# USB-UART-Converter.net
KiCad netlist of a schematic drawn in Altium Designer
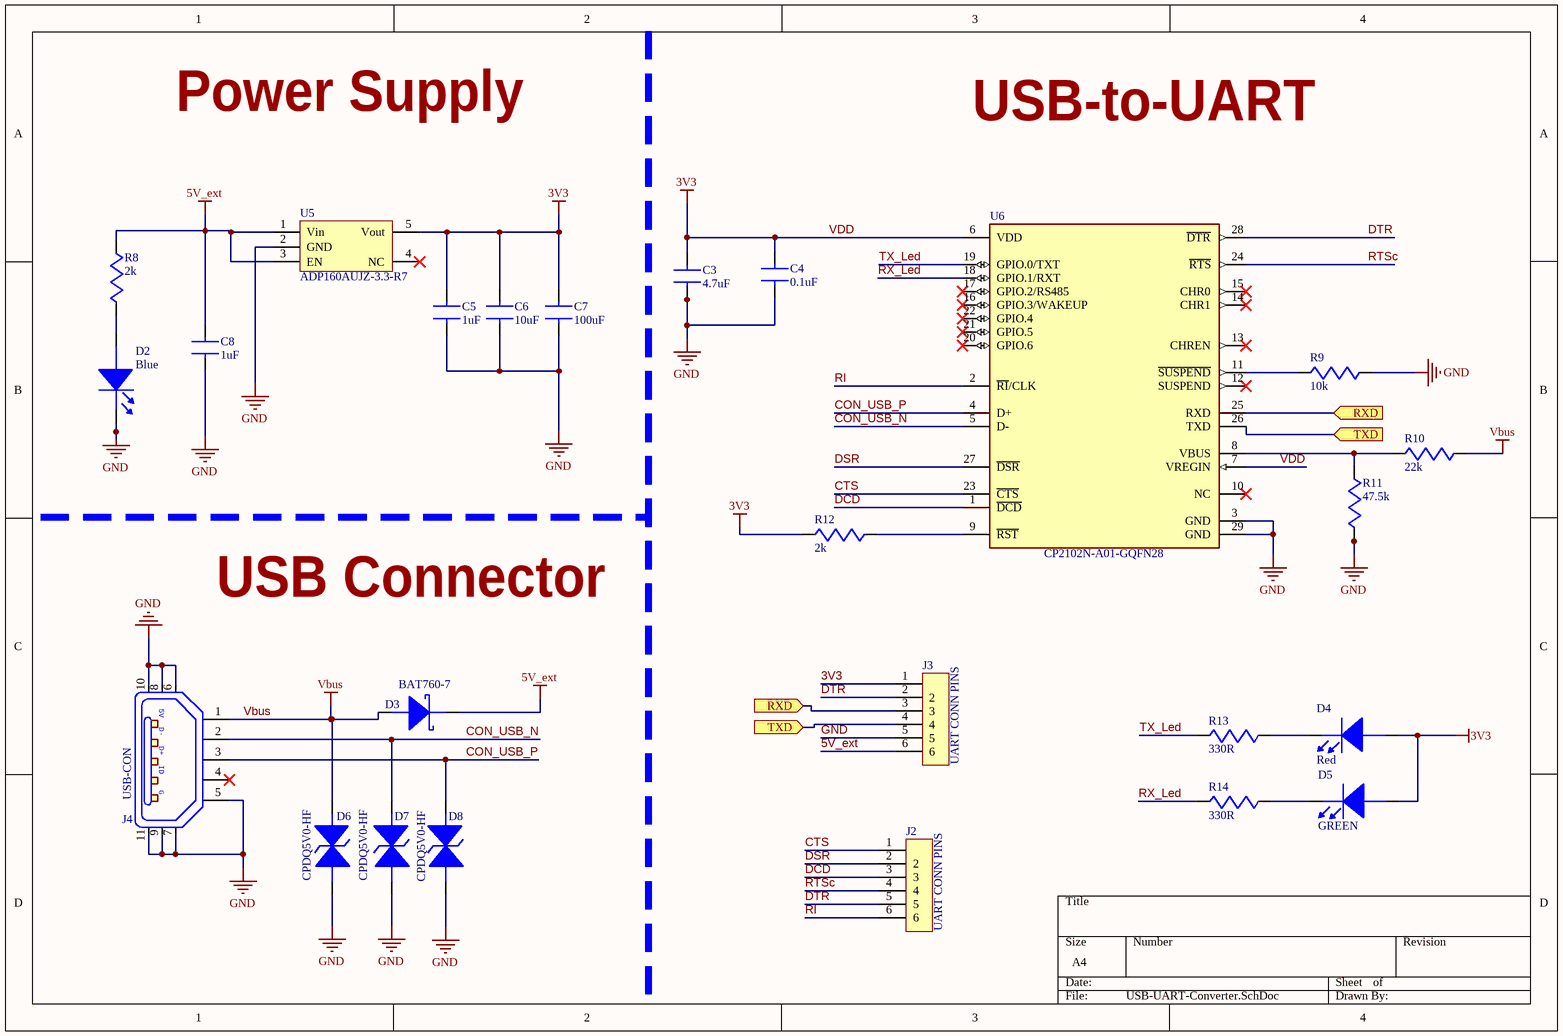
[diagram p0: USB-UART-Converter.SchDoc]

(export (version "E")
  (design (tool "Eeschema 10.0.6"))
  (components
    (comp (ref "C3")
      (value "4.7uF")
      (footprint "C0603")
      (fields
        (field (name "MANUFACTURER") "KEMET")
        (field (name "MANUFACTURER PART NUMBER") "C0603C475K9PACTU")
        (field (name "TOLERANCE") "10%")
      )
      (libsource (lib "Iot_board_schlib") (part "C0603C475K9PACTU"))
    )
    (comp (ref "C4")
      (value "0.1uF")
      (footprint "C0603")
      (fields
        (field (name "MANUFACTURER") "KEMET")
        (field (name "MANUFACTURER PART NUMBER") "C0603C104K5RACTU")
        (field (name "TOLERANCE") "10%")
      )
      (libsource (lib "Iot_board_schlib") (part "C0603C104K5RACTU"))
    )
    (comp (ref "C5")
      (value "1uF")
      (footprint "C0603")
      (description "Cap Ceramic 1uF 10V X5R 10% SMD 0603 85°C Paper T/R")
      (fields
        (field (name "MANUFACTURER") "KEMET")
        (field (name "MANUFACTURER PART NUMBER") "C0603C105K8PACTU")
      )
      (libsource (lib "Iot_board_schlib") (part "C0603C105K8PACTU"))
    )
    (comp (ref "C6")
      (value "10uF")
      (footprint "C0603")
      (description "KEMET - C0603C106M9PACTU - CAP, MLCC, X5R, 10UF, 6.3V, 0603")
      (fields
        (field (name "MANUFACTURER") "KEMET")
        (field (name "MANUFACTURER PART NUMBER") "C0603C106M9PACTU")
      )
      (libsource (lib "Iot_board_schlib") (part "C0603C106M9PACTU"))
    )
    (comp (ref "C7")
      (value "100uF")
      (footprint "C1206")
      (description "KEMET - C1206C107M9PACTU - CAP, 100µF, 6.3V, 20%, X5R, 1206")
      (fields
        (field (name "MANUFACTURER") "KEMET")
        (field (name "MANUFACTURER PART NUMBER") "C1206C107M9PACTU")
      )
      (libsource (lib "Iot_board_schlib") (part "C1206C107M9PACTU"))
    )
    (comp (ref "C8")
      (value "1uF")
      (footprint "C0603")
      (description "Cap Ceramic 1uF 10V X5R 10% SMD 0603 85°C Paper T/R")
      (fields
        (field (name "MANUFACTURER") "KEMET")
        (field (name "MANUFACTURER PART NUMBER") "C0603C105K8PACTU")
      )
      (libsource (lib "Iot_board_schlib") (part "C0603C105K8PACTU"))
    )
    (comp (ref "D2")
      (value "Blue")
      (footprint "LED_0603")
      (description "LED BLUE CLEAR 0603 SMD")
      (fields
        (field (name "MANUFACTURER") "Vishay Lite-On")
        (field (name "MANUFACTURER PART NUMBER") "LTST-C191TBKT")
      )
      (libsource (lib "Iot_board_schlib") (part "LTST-C191TBKT"))
    )
    (comp (ref "D3")
      (value "BAT760-7")
      (footprint "SOD323")
      (description "DIODE SCHOTTKY 30V 1A SOD323")
      (fields (field (name "MANUFACTURER") "Diodes"))
      (libsource (lib "usb_uart_Schlib") (part "BAT760-7"))
    )
    (comp (ref "D4")
      (value "Red")
      (footprint "LED_0603")
      (description "AVAGO TECHNOLOGIES - HSMS-C190 - LED, RED, 10MCD, 626NM")
      (fields
        (field (name "MANUFACTURER") "Broadcom Avago")
        (field (name "MANUFACTURER PART NUMBER") "HSMS-C190")
      )
      (libsource (lib "Iot_board_schlib") (part "HSMS-C190"))
    )
    (comp (ref "D5")
      (value "GREEN")
      (footprint "LED_0603")
      (description "LED Uni-Color Green 572nm 2-Pin Chip 0603(1608Metric) T/R")
      (fields
        (field (name "MANUFACTURER") "Osram Opto")
        (field (name "MANUFACTURER PART NUMBER") "LGL29K-G2J1-24-Z")
      )
      (libsource (lib "usb_uart_Schlib") (part "LGL29K-G2J1-24-Z"))
    )
    (comp (ref "D6")
      (value "CPDQ5V0-HF")
      (footprint "SOD-923F")
      (description "TVS DIODE 5V 18.6V 0402/SOD923F")
      (fields (field (name "MANUFACTURER") "Comchip"))
      (libsource (lib "usb_uart_Schlib") (part "CPDQ5V0-HF"))
    )
    (comp (ref "D7")
      (value "CPDQ5V0-HF")
      (footprint "SOD-923F")
      (description "TVS DIODE 5V 18.6V 0402/SOD923F")
      (fields (field (name "MANUFACTURER") "Comchip"))
      (libsource (lib "usb_uart_Schlib") (part "CPDQ5V0-HF"))
    )
    (comp (ref "D8")
      (value "CPDQ5V0-HF")
      (footprint "SOD-923F")
      (description "TVS DIODE 5V 18.6V 0402/SOD923F")
      (fields (field (name "MANUFACTURER") "Comchip"))
      (libsource (lib "usb_uart_Schlib") (part "CPDQ5V0-HF"))
    )
    (comp (ref "J2")
      (value "UART CONN PINS")
      (footprint "HDR_FEMALE_1x6_2.54mm")
      (fields
        (field (name "MANUFACTURER") "Amphenol FCI")
        (field (name "MANUFACTURER PART NUMBER") "66951-010LF")
      )
      (libsource (lib "usb_uart_Schlib") (part "UART CONN PINS"))
    )
    (comp (ref "J3")
      (value "UART CONN PINS")
      (footprint "HDR_FEMALE_1x6_2.54mm")
      (fields
        (field (name "MANUFACTURER") "Amphenol FCI")
        (field (name "MANUFACTURER PART NUMBER") "66951-010LF")
      )
      (libsource (lib "usb_uart_Schlib") (part "UART CONN PINS"))
    )
    (comp (ref "J4")
      (value "USB-CON")
      (footprint "10118193")
      (description "CONN USB MICRO B RECPT SMT R/A")
      (fields
        (field (name "MANUFACTURER") "Amphenol FCI")
        (field (name "MANUFACTURER PART NUMBER") "10118193-0001LF")
      )
      (libsource (lib "usb_uart_Schlib") (part "10118193-0001LF"))
    )
    (comp (ref "R8")
      (value "2k")
      (footprint "R0603")
      (description "D11/CRCW0603 100 2K 1% ET1 e3")
      (fields
        (field (name "MANUFACTURER") "Vishay")
        (field (name "MANUFACTURER PART NUMBER") "CRCW06032K00FKEA")
      )
      (libsource (lib "Iot_board_schlib") (part "CRCW06032K00FKEA"))
    )
    (comp (ref "R9")
      (value "10k")
      (footprint "R0603")
      (fields
        (field (name "MANUFACTURER") "Vishay")
        (field (name "MANUFACTURER PART NUMBER") "CRCW060310K0FKEA")
        (field (name "TOLERANCE") "1%")
      )
      (libsource (lib "Iot_board_schlib") (part "CRCW060310K0FKEA"))
    )
    (comp (ref "R10")
      (value "22k")
      (footprint "R0603")
      (fields
        (field (name "MANUFACTURER") "Vishay")
        (field (name "MANUFACTURER PART NUMBER") "CRCW060322K0FKEA")
        (field (name "TOLERANCE") "1%")
      )
      (libsource (lib "Iot_board_schlib") (part "CRCW060322K0FKEA"))
    )
    (comp (ref "R11")
      (value "47.5k")
      (footprint "R0603")
      (description "Resistor;  Thick Film;  47.5 Kilohms;  0.1 W;  1%;  SMT;  0603;  TCR 37 ppm/DegC")
      (fields
        (field (name "MANUFACTURER") "Vishay")
        (field (name "MANUFACTURER PART NUMBER") "CRCW060347K5FKEA")
      )
      (libsource (lib "Iot_board_schlib") (part "CRCW060347K5FKEA"))
    )
    (comp (ref "R12")
      (value "2k")
      (footprint "R0603")
      (description "D11/CRCW0603 100 2K 1% ET1 e3")
      (fields
        (field (name "MANUFACTURER") "Vishay")
        (field (name "MANUFACTURER PART NUMBER") "CRCW06032K00FKEA")
      )
      (libsource (lib "Iot_board_schlib") (part "CRCW06032K00FKEA"))
    )
    (comp (ref "R13")
      (value "330R")
      (footprint "R0603")
      (description "Res Thick Film 0603 330K Ohm 1% 1/10W 100ppm/C Molded SMD Paper T/R")
      (fields
        (field (name "MANUFACTURER") "Vishay")
        (field (name "MANUFACTURER PART NUMBER") "CRCW0603330KFKEA")
      )
      (libsource (lib "Iot_board_schlib") (part "CRCW0603330KFKEA"))
    )
    (comp (ref "R14")
      (value "330R")
      (footprint "R0603")
      (description "Res Thick Film 0603 330K Ohm 1% 1/10W 100ppm/C Molded SMD Paper T/R")
      (fields
        (field (name "MANUFACTURER") "Vishay")
        (field (name "MANUFACTURER PART NUMBER") "CRCW0603330KFKEA")
      )
      (libsource (lib "Iot_board_schlib") (part "CRCW0603330KFKEA"))
    )
    (comp (ref "U5")
      (value "ADP160AUJZ-3.3-R7")
      (footprint "SOT95")
      (fields (field (name "MANUFACTURER") "Analog Devices"))
      (libsource (lib "Iot_board_schlib") (part "ADP160AUJZ-3.3-R7"))
    )
    (comp (ref "U6")
      (value "CP2102N-A01-GQFN28")
      (footprint "FP-CP2102N-A01-GQFN28-IPC_A")
      (description "IC BRIDGE USB TO UART 28QFN")
      (fields (field (name "MANUFACTURER") "Silicon Labs"))
      (libsource (lib "usb_uart_Schlib") (part "CP2102N-A01-GQFN28"))
    )
  )
  (nets
    (net (code "1") (name "/CON_USB_N") (class "Default")
      (node (ref "D7") (pin "1") (pinfunction "Cathode_1") (pintype "passive"))
      (node (ref "J4") (pin "2") (pinfunction "2_2") (pintype "passive"))
      (node (ref "U6") (pin "5") (pinfunction "D-_5") (pintype "passive"))
    )
    (net (code "2") (name "/CON_USB_P") (class "Default")
      (node (ref "D8") (pin "1") (pinfunction "Cathode_1") (pintype "passive"))
      (node (ref "J4") (pin "3") (pinfunction "3_3") (pintype "passive"))
      (node (ref "U6") (pin "4") (pinfunction "D+_4") (pintype "passive"))
    )
    (net (code "3") (name "/CTS") (class "Default")
      (node (ref "J2") (pin "1") (pintype "passive"))
      (node (ref "U6") (pin "23") (pinfunction "~{CTS}_23") (pintype "passive"))
    )
    (net (code "4") (name "/DCD") (class "Default")
      (node (ref "J2") (pin "3") (pinfunction "3_3") (pintype "passive"))
      (node (ref "U6") (pin "1") (pinfunction "~{DCD}_1") (pintype "passive"))
    )
    (net (code "5") (name "/DSR") (class "Default")
      (node (ref "J2") (pin "2") (pinfunction "2_2") (pintype "passive"))
      (node (ref "U6") (pin "27") (pinfunction "~{DSR}_27") (pintype "passive"))
    )
    (net (code "6") (name "/DTR") (class "Default")
      (node (ref "J2") (pin "5") (pinfunction "5_5") (pintype "passive"))
      (node (ref "J3") (pin "2") (pinfunction "2_2") (pintype "passive"))
      (node (ref "U6") (pin "28") (pinfunction "~{DTR}_28") (pintype "output"))
    )
    (net (code "7") (name "/RI") (class "Default")
      (node (ref "J2") (pin "6") (pinfunction "6_6") (pintype "passive"))
      (node (ref "U6") (pin "2") (pinfunction "~{RI}/CLK_2") (pintype "passive"))
    )
    (net (code "8") (name "/RTSc") (class "Default")
      (node (ref "J2") (pin "4") (pinfunction "4_4") (pintype "passive"))
      (node (ref "U6") (pin "24") (pinfunction "~{RTS}_24") (pintype "output"))
    )
    (net (code "9") (name "/RXD") (class "Default")
      (node (ref "J3") (pin "3") (pinfunction "3_3") (pintype "passive"))
      (node (ref "U6") (pin "25") (pinfunction "RXD_25") (pintype "passive"))
    )
    (net (code "10") (name "/RX_Led") (class "Default")
      (node (ref "R14") (pin "1") (pinfunction "1_1") (pintype "passive"))
      (node (ref "U6") (pin "18") (pinfunction "GPIO.1/RXT_18") (pintype "bidirectional"))
    )
    (net (code "11") (name "/TXD") (class "Default")
      (node (ref "J3") (pin "4") (pinfunction "4_4") (pintype "passive"))
      (node (ref "U6") (pin "26") (pinfunction "TXD_26") (pintype "passive"))
    )
    (net (code "12") (name "/TX_Led") (class "Default")
      (node (ref "R13") (pin "1") (pinfunction "1_1") (pintype "passive"))
      (node (ref "U6") (pin "19") (pinfunction "GPIO.0/TXT_19") (pintype "bidirectional"))
    )
    (net (code "13") (name "3V3") (class "Default")
      (node (ref "C3") (pin "2") (pinfunction "2_2") (pintype "passive"))
      (node (ref "C4") (pin "2") (pinfunction "2_2") (pintype "passive"))
      (node (ref "C5") (pin "2") (pinfunction "2_2") (pintype "passive"))
      (node (ref "C6") (pin "2") (pinfunction "2_2") (pintype "passive"))
      (node (ref "C7") (pin "2") (pinfunction "2_2") (pintype "passive"))
      (node (ref "D4") (pin "2") (pinfunction "Anode_2") (pintype "passive"))
      (node (ref "D5") (pin "2") (pinfunction "Anode_2") (pintype "passive"))
      (node (ref "J3") (pin "1") (pintype "passive"))
      (node (ref "R12") (pin "1") (pinfunction "1_1") (pintype "passive"))
      (node (ref "U5") (pin "5") (pinfunction "Vout_5") (pintype "passive"))
      (node (ref "U6") (pin "6") (pinfunction "VDD_6") (pintype "power_in"))
      (node (ref "U6") (pin "7") (pinfunction "VREGIN_7") (pintype "input"))
    )
    (net (code "14") (name "5V_ext") (class "Default")
      (node (ref "C8") (pin "2") (pinfunction "2_2") (pintype "passive"))
      (node (ref "D3") (pin "1") (pinfunction "Cathode_1") (pintype "passive"))
      (node (ref "J3") (pin "6") (pinfunction "6_6") (pintype "passive"))
      (node (ref "R8") (pin "2") (pinfunction "2_2") (pintype "passive"))
      (node (ref "U5") (pin "1") (pinfunction "Vin_1") (pintype "passive"))
      (node (ref "U5") (pin "3") (pinfunction "EN_3") (pintype "passive"))
    )
    (net (code "15") (name "GND") (class "Default")
      (node (ref "C3") (pin "1") (pinfunction "1_1") (pintype "passive"))
      (node (ref "C4") (pin "1") (pinfunction "1_1") (pintype "passive"))
      (node (ref "C5") (pin "1") (pinfunction "1_1") (pintype "passive"))
      (node (ref "C6") (pin "1") (pinfunction "1_1") (pintype "passive"))
      (node (ref "C7") (pin "1") (pinfunction "1_1") (pintype "passive"))
      (node (ref "C8") (pin "1") (pinfunction "1_1") (pintype "passive"))
      (node (ref "D2") (pin "1") (pinfunction "Cathode_1") (pintype "passive"))
      (node (ref "D6") (pin "2") (pinfunction "Anode_2") (pintype "passive"))
      (node (ref "D7") (pin "2") (pinfunction "Anode_2") (pintype "passive"))
      (node (ref "D8") (pin "2") (pinfunction "Anode_2") (pintype "passive"))
      (node (ref "J3") (pin "5") (pinfunction "5_5") (pintype "passive"))
      (node (ref "J4") (pin "10") (pinfunction "10_10") (pintype "passive"))
      (node (ref "J4") (pin "11") (pinfunction "11_11") (pintype "passive"))
      (node (ref "J4") (pin "5") (pinfunction "5_5") (pintype "passive"))
      (node (ref "J4") (pin "6") (pinfunction "6_6") (pintype "passive"))
      (node (ref "J4") (pin "7") (pinfunction "7_7") (pintype "passive"))
      (node (ref "J4") (pin "8") (pinfunction "8_8") (pintype "passive"))
      (node (ref "J4") (pin "9") (pinfunction "9_9") (pintype "passive"))
      (node (ref "R11") (pin "1") (pinfunction "1_1") (pintype "passive"))
      (node (ref "R9") (pin "2") (pinfunction "2_2") (pintype "passive"))
      (node (ref "U5") (pin "2") (pinfunction "GND_2") (pintype "passive"))
      (node (ref "U6") (pin "29") (pinfunction "GND_29") (pintype "power_in"))
      (node (ref "U6") (pin "3") (pinfunction "GND_3") (pintype "power_in"))
    )
    (net (code "16") (name "Net-(D2-Anode)") (class "Default")
      (node (ref "D2") (pin "2") (pinfunction "Anode_2") (pintype "passive"))
      (node (ref "R8") (pin "1") (pinfunction "1_1") (pintype "passive"))
    )
    (net (code "17") (name "Net-(D4-Cathode)") (class "Default")
      (node (ref "D4") (pin "1") (pinfunction "Cathode_1") (pintype "passive"))
      (node (ref "R13") (pin "2") (pinfunction "2_2") (pintype "passive"))
    )
    (net (code "18") (name "Net-(D5-Cathode)") (class "Default")
      (node (ref "D5") (pin "1") (pinfunction "Cathode_1") (pintype "passive"))
      (node (ref "R14") (pin "2") (pinfunction "2_2") (pintype "passive"))
    )
    (net (code "19") (name "Net-(U6-VBUS)") (class "Default")
      (node (ref "R10") (pin "1") (pinfunction "1_1") (pintype "passive"))
      (node (ref "R11") (pin "2") (pinfunction "2_2") (pintype "passive"))
      (node (ref "U6") (pin "8") (pinfunction "VBUS_8") (pintype "passive"))
    )
    (net (code "20") (name "Net-(U6-~{RST})") (class "Default")
      (node (ref "R12") (pin "2") (pinfunction "2_2") (pintype "passive"))
      (node (ref "U6") (pin "9") (pinfunction "~{RST}_9") (pintype "passive"))
    )
    (net (code "21") (name "Net-(U6-~{SUSPEND})") (class "Default")
      (node (ref "R9") (pin "1") (pinfunction "1_1") (pintype "passive"))
      (node (ref "U6") (pin "11") (pinfunction "~{SUSPEND}_11") (pintype "output"))
    )
    (net (code "22") (name "Vbus") (class "Default")
      (node (ref "D3") (pin "2") (pinfunction "Anode_2") (pintype "passive"))
      (node (ref "D6") (pin "1") (pinfunction "Cathode_1") (pintype "passive"))
      (node (ref "J4") (pin "1") (pinfunction "1_1") (pintype "passive"))
      (node (ref "R10") (pin "2") (pinfunction "2_2") (pintype "passive"))
    )
    (net (code "23") (name "unconnected-(J4-Pad4)") (class "Default")
      (node (ref "J4") (pin "4") (pinfunction "4_4") (pintype "passive+no_connect"))
    )
    (net (code "24") (name "unconnected-(U5-NC-Pad4)") (class "Default")
      (node (ref "U5") (pin "4") (pinfunction "NC_4") (pintype "passive+no_connect"))
    )
    (net (code "25") (name "unconnected-(U6-CHR0-Pad15)") (class "Default")
      (node (ref "U6") (pin "15") (pinfunction "CHR0_15") (pintype "output+no_connect"))
    )
    (net (code "26") (name "unconnected-(U6-CHR1-Pad14)") (class "Default")
      (node (ref "U6") (pin "14") (pinfunction "CHR1_14") (pintype "output+no_connect"))
    )
    (net (code "27") (name "unconnected-(U6-CHREN-Pad13)") (class "Default")
      (node (ref "U6") (pin "13") (pinfunction "CHREN_13") (pintype "output+no_connect"))
    )
    (net (code "28") (name "unconnected-(U6-GPIO.2{slash}RS485-Pad17)") (class "Default")
      (node (ref "U6") (pin "17") (pinfunction "GPIO.2/RS485_17") (pintype "bidirectional+no_connect"))
    )
    (net (code "29") (name "unconnected-(U6-GPIO.3{slash}WAKEUP-Pad16)") (class "Default")
      (node (ref "U6") (pin "16") (pinfunction "GPIO.3/WAKEUP_16") (pintype "bidirectional+no_connect"))
    )
    (net (code "30") (name "unconnected-(U6-GPIO.4-Pad22)") (class "Default")
      (node (ref "U6") (pin "22") (pinfunction "GPIO.4_22") (pintype "bidirectional+no_connect"))
    )
    (net (code "31") (name "unconnected-(U6-GPIO.5-Pad21)") (class "Default")
      (node (ref "U6") (pin "21") (pinfunction "GPIO.5_21") (pintype "bidirectional+no_connect"))
    )
    (net (code "32") (name "unconnected-(U6-GPIO.6-Pad20)") (class "Default")
      (node (ref "U6") (pin "20") (pinfunction "GPIO.6_20") (pintype "bidirectional+no_connect"))
    )
    (net (code "33") (name "unconnected-(U6-NC-Pad10)") (class "Default")
      (node (ref "U6") (pin "10") (pinfunction "NC_10") (pintype "passive+no_connect"))
    )
    (net (code "34") (name "unconnected-(U6-SUSPEND-Pad12)") (class "Default")
      (node (ref "U6") (pin "12") (pinfunction "SUSPEND_12") (pintype "output+no_connect"))
    )
  )
)
